# air_cylinder_control.net
KiCad netlist of a schematic drawn in Altium Designer
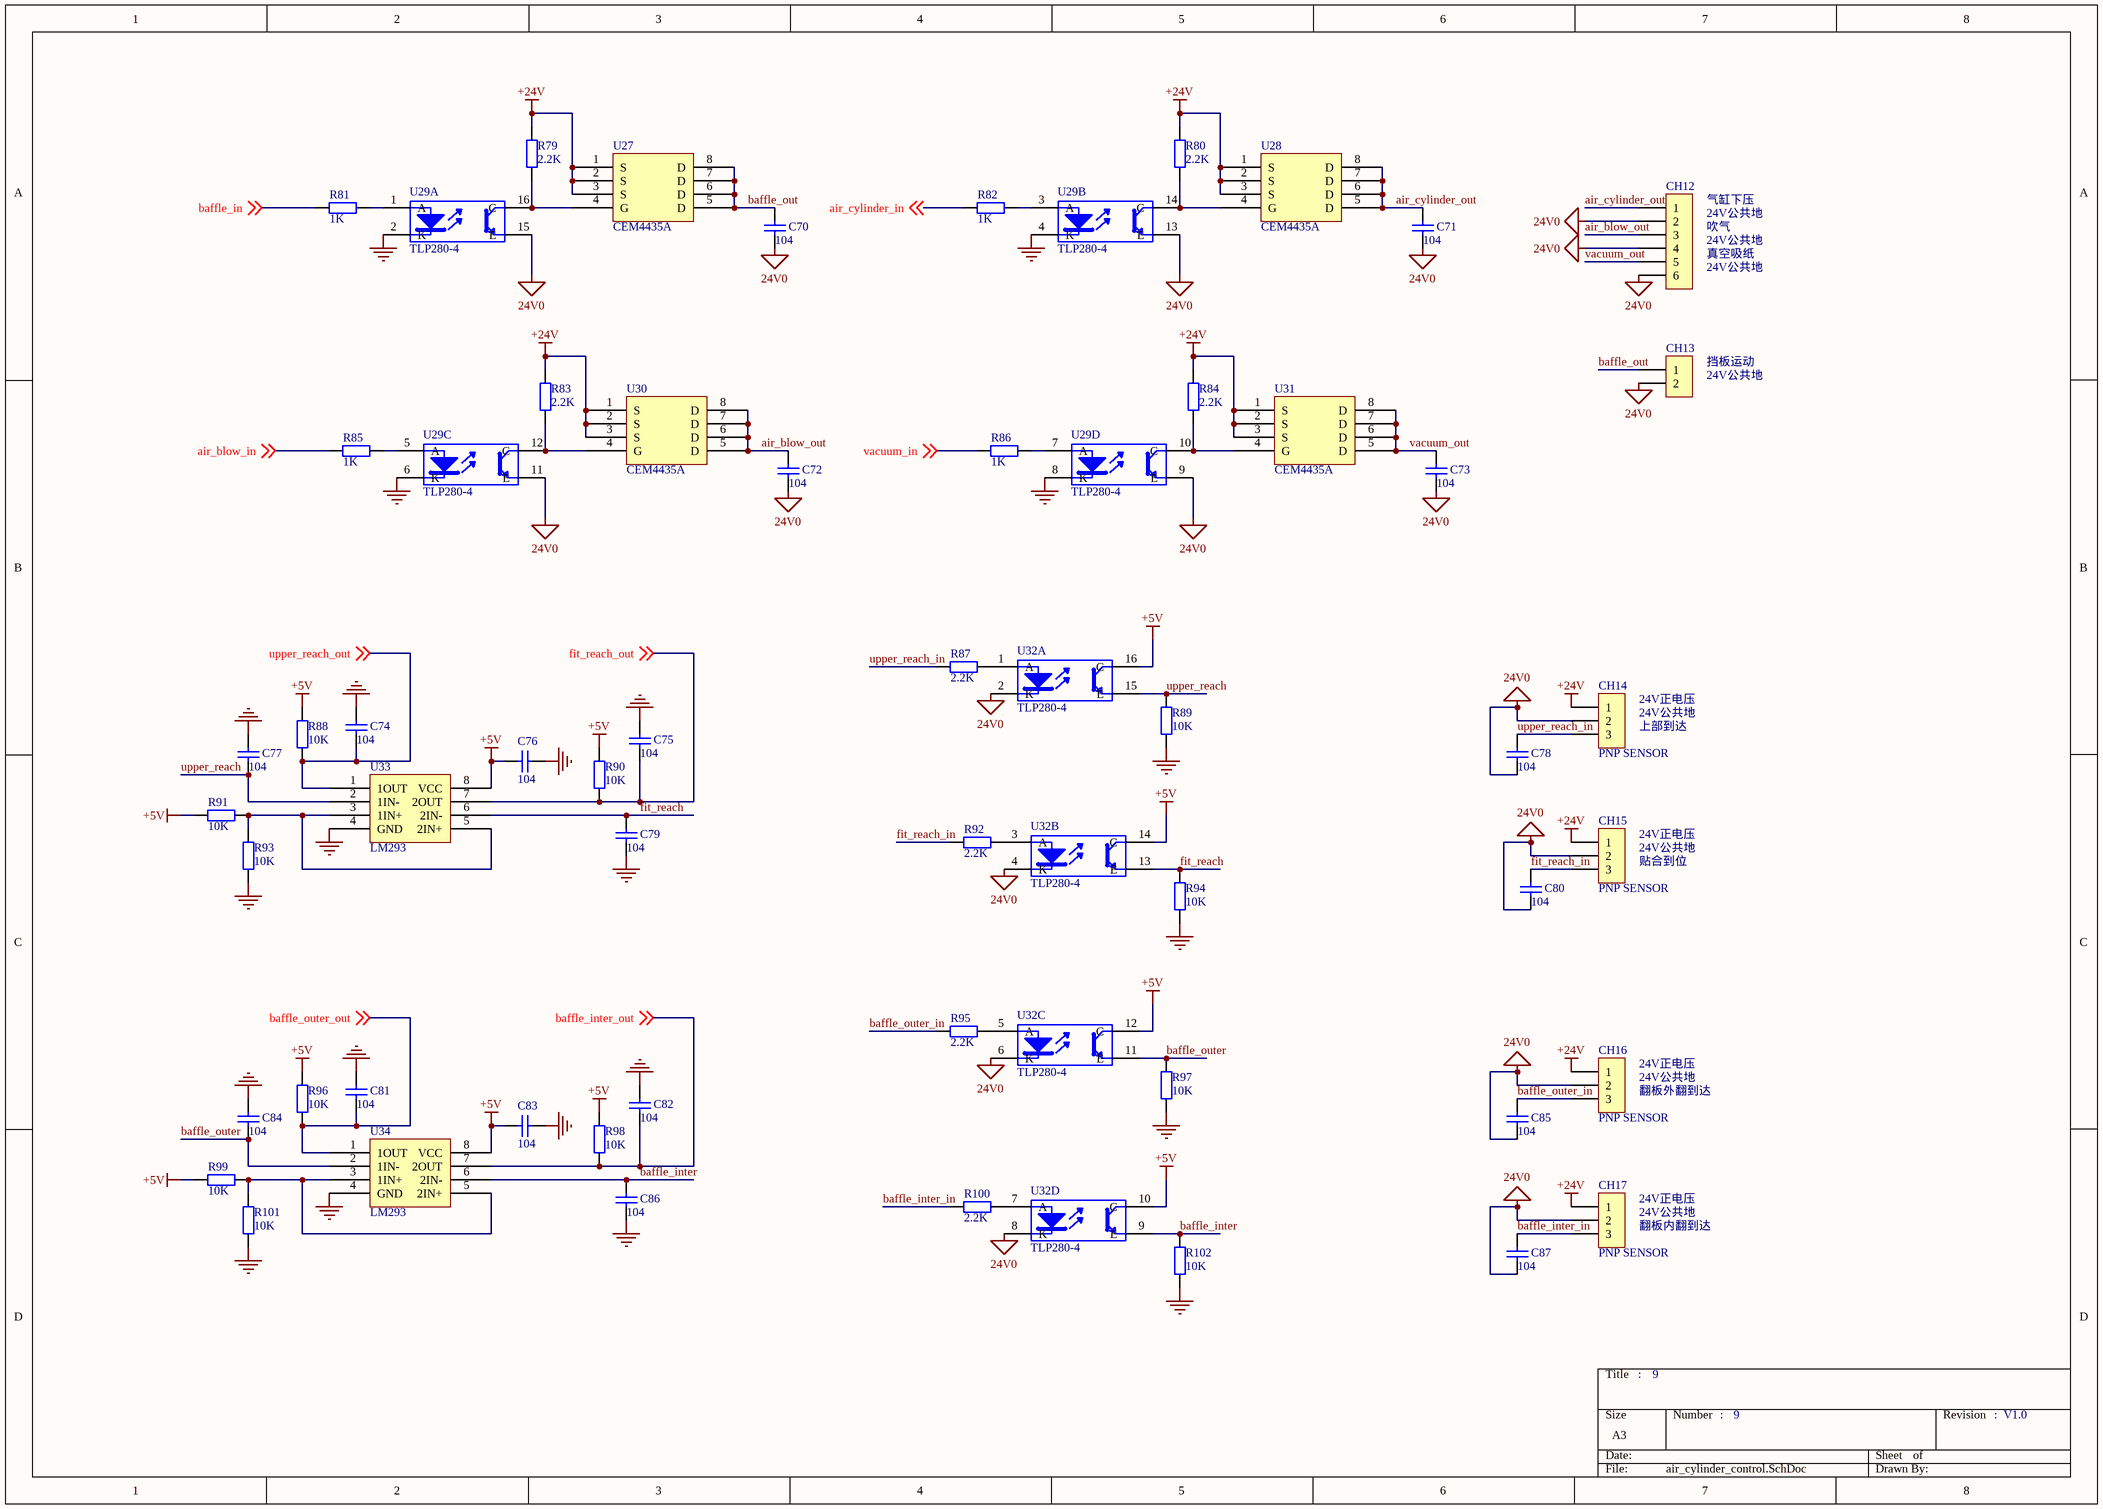
[diagram p0: air_cylinder_control.SchDoc]

(export (version "E")
  (design (tool "Eeschema 10.0.6"))
  (components
    (comp (ref "C70")
      (value "104")
      (footprint "0805")
      (description "Capacitor")
      (fields (field (name "Comment") "Cap") (field (name "PUBLISHER") "Altium Limited"))
      (libsource (lib "Miscellaneous Devices") (part "Cap"))
    )
    (comp (ref "C71")
      (value "104")
      (footprint "0805")
      (description "Capacitor")
      (fields (field (name "Comment") "Cap") (field (name "PUBLISHER") "Altium Limited"))
      (libsource (lib "Miscellaneous Devices") (part "Cap"))
    )
    (comp (ref "C72")
      (value "104")
      (footprint "0805")
      (description "Capacitor")
      (fields (field (name "Comment") "Cap") (field (name "PUBLISHER") "Altium Limited"))
      (libsource (lib "Miscellaneous Devices") (part "Cap"))
    )
    (comp (ref "C73")
      (value "104")
      (footprint "0805")
      (description "Capacitor")
      (fields (field (name "Comment") "Cap") (field (name "PUBLISHER") "Altium Limited"))
      (libsource (lib "Miscellaneous Devices") (part "Cap"))
    )
    (comp (ref "C74")
      (value "104")
      (footprint "0805")
      (description "Capacitor")
      (fields (field (name "Comment") "Cap") (field (name "PUBLISHER") "Altium Limited"))
      (libsource (lib "Miscellaneous Devices") (part "Cap"))
    )
    (comp (ref "C75")
      (value "104")
      (footprint "0805")
      (description "Capacitor")
      (fields (field (name "Comment") "Cap") (field (name "PUBLISHER") "Altium Limited"))
      (libsource (lib "Miscellaneous Devices") (part "Cap"))
    )
    (comp (ref "C76")
      (value "104")
      (footprint "0805")
      (description "Capacitor")
      (fields (field (name "Comment") "Cap") (field (name "PUBLISHER") "Altium Limited"))
      (libsource (lib "Miscellaneous Devices") (part "Cap"))
    )
    (comp (ref "C77")
      (value "104")
      (footprint "0805")
      (description "Capacitor")
      (fields (field (name "Comment") "Cap") (field (name "PUBLISHER") "Altium Limited"))
      (libsource (lib "Miscellaneous Devices") (part "Cap"))
    )
    (comp (ref "C78")
      (value "104")
      (footprint "0805")
      (description "Capacitor")
      (fields (field (name "Comment") "Cap") (field (name "PUBLISHER") "Altium Limited"))
      (libsource (lib "Miscellaneous Devices") (part "Cap"))
    )
    (comp (ref "C79")
      (value "104")
      (footprint "0805")
      (description "Capacitor")
      (fields (field (name "Comment") "Cap") (field (name "PUBLISHER") "Altium Limited"))
      (libsource (lib "Miscellaneous Devices") (part "Cap"))
    )
    (comp (ref "C80")
      (value "104")
      (footprint "0805")
      (description "Capacitor")
      (fields (field (name "Comment") "Cap") (field (name "PUBLISHER") "Altium Limited"))
      (libsource (lib "Miscellaneous Devices") (part "Cap"))
    )
    (comp (ref "C81")
      (value "104")
      (footprint "0805")
      (description "Capacitor")
      (fields (field (name "Comment") "Cap") (field (name "PUBLISHER") "Altium Limited"))
      (libsource (lib "Miscellaneous Devices") (part "Cap"))
    )
    (comp (ref "C82")
      (value "104")
      (footprint "0805")
      (description "Capacitor")
      (fields (field (name "Comment") "Cap") (field (name "PUBLISHER") "Altium Limited"))
      (libsource (lib "Miscellaneous Devices") (part "Cap"))
    )
    (comp (ref "C83")
      (value "104")
      (footprint "0805")
      (description "Capacitor")
      (fields (field (name "Comment") "Cap") (field (name "PUBLISHER") "Altium Limited"))
      (libsource (lib "Miscellaneous Devices") (part "Cap"))
    )
    (comp (ref "C84")
      (value "104")
      (footprint "0805")
      (description "Capacitor")
      (fields (field (name "Comment") "Cap") (field (name "PUBLISHER") "Altium Limited"))
      (libsource (lib "Miscellaneous Devices") (part "Cap"))
    )
    (comp (ref "C85")
      (value "104")
      (footprint "0805")
      (description "Capacitor")
      (fields (field (name "Comment") "Cap") (field (name "PUBLISHER") "Altium Limited"))
      (libsource (lib "Miscellaneous Devices") (part "Cap"))
    )
    (comp (ref "C86")
      (value "104")
      (footprint "0805")
      (description "Capacitor")
      (fields (field (name "Comment") "Cap") (field (name "PUBLISHER") "Altium Limited"))
      (libsource (lib "Miscellaneous Devices") (part "Cap"))
    )
    (comp (ref "C87")
      (value "104")
      (footprint "0805")
      (description "Capacitor")
      (fields (field (name "Comment") "Cap") (field (name "PUBLISHER") "Altium Limited"))
      (libsource (lib "Miscellaneous Devices") (part "Cap"))
    )
    (comp (ref "CH12")
      (value "HEADER1X6")
      (footprint "CH3.96-6PIN")
      (libsource (lib "myIntegrated_Library1") (part "HEADER1X6"))
    )
    (comp (ref "CH13")
      (value "HEADER1X2")
      (footprint "CH3.96-2PIN")
      (libsource (lib "myIntegrated_Library1") (part "HEADER1X2"))
    )
    (comp (ref "CH14")
      (value "HEADER1X3")
      (footprint "CH3.96-3PIN")
      (fields (field (name "ALTIUM_UNNAMED_1") "PNP SENSOR"))
      (libsource (lib "myIntegrated_Library1") (part "HEADER1X3"))
    )
    (comp (ref "CH15")
      (value "HEADER1X3")
      (footprint "CH3.96-3PIN")
      (fields (field (name "ALTIUM_UNNAMED_1") "PNP SENSOR"))
      (libsource (lib "myIntegrated_Library1") (part "HEADER1X3"))
    )
    (comp (ref "CH16")
      (value "HEADER1X3")
      (footprint "CH3.96-3PIN")
      (fields (field (name "ALTIUM_UNNAMED_1") "PNP SENSOR"))
      (libsource (lib "myIntegrated_Library1") (part "HEADER1X3"))
    )
    (comp (ref "CH17")
      (value "HEADER1X3")
      (footprint "CH3.96-3PIN")
      (fields (field (name "ALTIUM_UNNAMED_1") "PNP SENSOR"))
      (libsource (lib "myIntegrated_Library1") (part "HEADER1X3"))
    )
    (comp (ref "R79")
      (value "2.2K")
      (footprint "0805")
      (description "Resistor")
      (fields (field (name "Comment") "Res2") (field (name "PUBLISHER") "Altium Limited"))
      (libsource (lib "Miscellaneous Devices") (part "Res2"))
    )
    (comp (ref "R80")
      (value "2.2K")
      (footprint "0805")
      (description "Resistor")
      (fields (field (name "Comment") "Res2") (field (name "PUBLISHER") "Altium Limited"))
      (libsource (lib "Miscellaneous Devices") (part "Res2"))
    )
    (comp (ref "R81")
      (value "1K")
      (footprint "0805")
      (description "Resistor")
      (fields (field (name "Comment") "Res2") (field (name "PUBLISHER") "Altium Limited"))
      (libsource (lib "") (part "Res2_1"))
    )
    (comp (ref "R82")
      (value "1K")
      (footprint "0805")
      (description "Resistor")
      (fields (field (name "Comment") "Res2") (field (name "PUBLISHER") "Altium Limited"))
      (libsource (lib "") (part "Res2_1"))
    )
    (comp (ref "R83")
      (value "2.2K")
      (footprint "0805")
      (description "Resistor")
      (fields (field (name "Comment") "Res2") (field (name "PUBLISHER") "Altium Limited"))
      (libsource (lib "Miscellaneous Devices") (part "Res2"))
    )
    (comp (ref "R84")
      (value "2.2K")
      (footprint "0805")
      (description "Resistor")
      (fields (field (name "Comment") "Res2") (field (name "PUBLISHER") "Altium Limited"))
      (libsource (lib "Miscellaneous Devices") (part "Res2"))
    )
    (comp (ref "R85")
      (value "1K")
      (footprint "0805")
      (description "Resistor")
      (fields (field (name "Comment") "Res2") (field (name "PUBLISHER") "Altium Limited"))
      (libsource (lib "") (part "Res2_1"))
    )
    (comp (ref "R86")
      (value "1K")
      (footprint "0805")
      (description "Resistor")
      (fields (field (name "Comment") "Res2") (field (name "PUBLISHER") "Altium Limited"))
      (libsource (lib "") (part "Res2_1"))
    )
    (comp (ref "R87")
      (value "2.2K")
      (footprint "0805")
      (description "Resistor")
      (fields (field (name "Comment") "Res2") (field (name "PUBLISHER") "Altium Limited"))
      (libsource (lib "") (part "Res2_1"))
    )
    (comp (ref "R88")
      (value "10K")
      (footprint "0805")
      (description "Resistor")
      (fields (field (name "Comment") "Res2") (field (name "PUBLISHER") "Altium Limited"))
      (libsource (lib "") (part "Res2_3"))
    )
    (comp (ref "R89")
      (value "10K")
      (footprint "0805")
      (description "Resistor")
      (fields (field (name "Comment") "Res2") (field (name "PUBLISHER") "Altium Limited"))
      (libsource (lib "") (part "Res2_3"))
    )
    (comp (ref "R90")
      (value "10K")
      (footprint "0805")
      (description "Resistor")
      (fields (field (name "Comment") "Res2") (field (name "PUBLISHER") "Altium Limited"))
      (libsource (lib "") (part "Res2_3"))
    )
    (comp (ref "R91")
      (value "10K")
      (footprint "0805")
      (description "Resistor")
      (fields (field (name "Comment") "Res2") (field (name "PUBLISHER") "Altium Limited"))
      (libsource (lib "") (part "Res2_2"))
    )
    (comp (ref "R92")
      (value "2.2K")
      (footprint "0805")
      (description "Resistor")
      (fields (field (name "Comment") "Res2") (field (name "PUBLISHER") "Altium Limited"))
      (libsource (lib "") (part "Res2_1"))
    )
    (comp (ref "R93")
      (value "10K")
      (footprint "0805")
      (description "Resistor")
      (fields (field (name "Comment") "Res2") (field (name "PUBLISHER") "Altium Limited"))
      (libsource (lib "") (part "Res2_3"))
    )
    (comp (ref "R94")
      (value "10K")
      (footprint "0805")
      (description "Resistor")
      (fields (field (name "Comment") "Res2") (field (name "PUBLISHER") "Altium Limited"))
      (libsource (lib "") (part "Res2_3"))
    )
    (comp (ref "R95")
      (value "2.2K")
      (footprint "0805")
      (description "Resistor")
      (fields (field (name "Comment") "Res2") (field (name "PUBLISHER") "Altium Limited"))
      (libsource (lib "") (part "Res2_1"))
    )
    (comp (ref "R96")
      (value "10K")
      (footprint "0805")
      (description "Resistor")
      (fields (field (name "Comment") "Res2") (field (name "PUBLISHER") "Altium Limited"))
      (libsource (lib "") (part "Res2_3"))
    )
    (comp (ref "R97")
      (value "10K")
      (footprint "0805")
      (description "Resistor")
      (fields (field (name "Comment") "Res2") (field (name "PUBLISHER") "Altium Limited"))
      (libsource (lib "") (part "Res2_3"))
    )
    (comp (ref "R98")
      (value "10K")
      (footprint "0805")
      (description "Resistor")
      (fields (field (name "Comment") "Res2") (field (name "PUBLISHER") "Altium Limited"))
      (libsource (lib "") (part "Res2_3"))
    )
    (comp (ref "R99")
      (value "10K")
      (footprint "0805")
      (description "Resistor")
      (fields (field (name "Comment") "Res2") (field (name "PUBLISHER") "Altium Limited"))
      (libsource (lib "") (part "Res2_2"))
    )
    (comp (ref "R100")
      (value "2.2K")
      (footprint "0805")
      (description "Resistor")
      (fields (field (name "Comment") "Res2") (field (name "PUBLISHER") "Altium Limited"))
      (libsource (lib "") (part "Res2_1"))
    )
    (comp (ref "R101")
      (value "10K")
      (footprint "0805")
      (description "Resistor")
      (fields (field (name "Comment") "Res2") (field (name "PUBLISHER") "Altium Limited"))
      (libsource (lib "") (part "Res2_3"))
    )
    (comp (ref "R102")
      (value "10K")
      (footprint "0805")
      (description "Resistor")
      (fields (field (name "Comment") "Res2") (field (name "PUBLISHER") "Altium Limited"))
      (libsource (lib "") (part "Res2_3"))
    )
    (comp (ref "U27")
      (value "CEM4435A")
      (footprint "SOP8-OP27")
      (libsource (lib "myIntegrated_Library1") (part "CEM4435A"))
    )
    (comp (ref "U28")
      (value "CEM4435A")
      (footprint "SOP8-OP27")
      (libsource (lib "myIntegrated_Library1") (part "CEM4435A"))
    )
    (comp (ref "U29") (value "TLP280-4") (footprint "SO16") (libsource (lib "WH V20") (part "TLP521-4")))
    (comp (ref "U30")
      (value "CEM4435A")
      (footprint "SOP8-OP27")
      (libsource (lib "myIntegrated_Library1") (part "CEM4435A"))
    )
    (comp (ref "U31")
      (value "CEM4435A")
      (footprint "SOP8-OP27")
      (libsource (lib "myIntegrated_Library1") (part "CEM4435A"))
    )
    (comp (ref "U32") (value "TLP280-4") (footprint "SO16") (libsource (lib "WH V20") (part "TLP521-4")))
    (comp (ref "U33")
      (value "LM293")
      (footprint "SOP8-OP27")
      (libsource (lib "myIntegrated_Library1") (part "LM293"))
    )
    (comp (ref "U34")
      (value "LM293")
      (footprint "SOP8-OP27")
      (libsource (lib "myIntegrated_Library1") (part "LM293"))
    )
  )
  (nets
    (net (code "1") (name "+5V") (class "Default")
      (node (ref "C76") (pin "2") (pinfunction "2_2") (pintype "passive"))
      (node (ref "C83") (pin "2") (pinfunction "2_2") (pintype "passive"))
      (node (ref "R88") (pin "2") (pinfunction "2_2") (pintype "passive"))
      (node (ref "R90") (pin "2") (pinfunction "2_2") (pintype "passive"))
      (node (ref "R91") (pin "2") (pinfunction "2_2") (pintype "passive"))
      (node (ref "R96") (pin "2") (pinfunction "2_2") (pintype "passive"))
      (node (ref "R98") (pin "2") (pinfunction "2_2") (pintype "passive"))
      (node (ref "R99") (pin "2") (pinfunction "2_2") (pintype "passive"))
      (node (ref "U32") (pin "10") (pinfunction "C_10") (pintype "passive"))
      (node (ref "U32") (pin "12") (pinfunction "C_12") (pintype "passive"))
      (node (ref "U32") (pin "14") (pinfunction "C_14") (pintype "passive"))
      (node (ref "U32") (pin "16") (pinfunction "C_16") (pintype "passive"))
      (node (ref "U33") (pin "8") (pinfunction "VCC_8") (pintype "passive"))
      (node (ref "U34") (pin "8") (pinfunction "VCC_8") (pintype "passive"))
    )
    (net (code "2") (name "+24V") (class "Default")
      (node (ref "CH14") (pin "1") (pinfunction "1_1") (pintype "passive"))
      (node (ref "CH15") (pin "1") (pinfunction "1_1") (pintype "passive"))
      (node (ref "CH16") (pin "1") (pinfunction "1_1") (pintype "passive"))
      (node (ref "CH17") (pin "1") (pinfunction "1_1") (pintype "passive"))
      (node (ref "R79") (pin "1") (pinfunction "1_1") (pintype "passive"))
      (node (ref "R80") (pin "1") (pinfunction "1_1") (pintype "passive"))
      (node (ref "R83") (pin "1") (pinfunction "1_1") (pintype "passive"))
      (node (ref "R84") (pin "1") (pinfunction "1_1") (pintype "passive"))
      (node (ref "U27") (pin "1") (pinfunction "S_1") (pintype "passive"))
      (node (ref "U27") (pin "2") (pinfunction "S_2") (pintype "passive"))
      (node (ref "U27") (pin "3") (pinfunction "S_3") (pintype "passive"))
      (node (ref "U28") (pin "1") (pinfunction "S_1") (pintype "passive"))
      (node (ref "U28") (pin "2") (pinfunction "S_2") (pintype "passive"))
      (node (ref "U28") (pin "3") (pinfunction "S_3") (pintype "passive"))
      (node (ref "U30") (pin "1") (pinfunction "S_1") (pintype "passive"))
      (node (ref "U30") (pin "2") (pinfunction "S_2") (pintype "passive"))
      (node (ref "U30") (pin "3") (pinfunction "S_3") (pintype "passive"))
      (node (ref "U31") (pin "1") (pinfunction "S_1") (pintype "passive"))
      (node (ref "U31") (pin "2") (pinfunction "S_2") (pintype "passive"))
      (node (ref "U31") (pin "3") (pinfunction "S_3") (pintype "passive"))
    )
    (net (code "3") (name "/air_blow_out") (class "Default")
      (node (ref "C72") (pin "2") (pinfunction "2_2") (pintype "passive"))
      (node (ref "CH12") (pin "3") (pinfunction "3_3") (pintype "passive"))
      (node (ref "U30") (pin "5") (pinfunction "D_5") (pintype "passive"))
      (node (ref "U30") (pin "6") (pinfunction "D_6") (pintype "passive"))
      (node (ref "U30") (pin "7") (pinfunction "D_7") (pintype "passive"))
      (node (ref "U30") (pin "8") (pinfunction "D_8") (pintype "passive"))
    )
    (net (code "4") (name "/air_cylinder_out") (class "Default")
      (node (ref "C71") (pin "2") (pinfunction "2_2") (pintype "passive"))
      (node (ref "CH12") (pin "1") (pinfunction "1_1") (pintype "passive"))
      (node (ref "U28") (pin "5") (pinfunction "D_5") (pintype "passive"))
      (node (ref "U28") (pin "6") (pinfunction "D_6") (pintype "passive"))
      (node (ref "U28") (pin "7") (pinfunction "D_7") (pintype "passive"))
      (node (ref "U28") (pin "8") (pinfunction "D_8") (pintype "passive"))
    )
    (net (code "5") (name "/baffle_inter") (class "Default")
      (node (ref "C86") (pin "2") (pinfunction "2_2") (pintype "passive"))
      (node (ref "R102") (pin "2") (pinfunction "2_2") (pintype "passive"))
      (node (ref "U32") (pin "9") (pinfunction "E_9") (pintype "passive"))
      (node (ref "U34") (pin "6") (pinfunction "2IN-_6") (pintype "passive"))
    )
    (net (code "6") (name "/baffle_inter_in") (class "Default")
      (node (ref "C87") (pin "2") (pinfunction "2_2") (pintype "passive"))
      (node (ref "CH17") (pin "3") (pinfunction "3_3") (pintype "passive"))
      (node (ref "R100") (pin "1") (pinfunction "1_1") (pintype "passive"))
    )
    (net (code "7") (name "/baffle_out") (class "Default")
      (node (ref "C70") (pin "2") (pinfunction "2_2") (pintype "passive"))
      (node (ref "CH13") (pin "1") (pinfunction "1_1") (pintype "passive"))
      (node (ref "U27") (pin "5") (pinfunction "D_5") (pintype "passive"))
      (node (ref "U27") (pin "6") (pinfunction "D_6") (pintype "passive"))
      (node (ref "U27") (pin "7") (pinfunction "D_7") (pintype "passive"))
      (node (ref "U27") (pin "8") (pinfunction "D_8") (pintype "passive"))
    )
    (net (code "8") (name "/baffle_outer") (class "Default")
      (node (ref "C84") (pin "1") (pinfunction "1_1") (pintype "passive"))
      (node (ref "R97") (pin "2") (pinfunction "2_2") (pintype "passive"))
      (node (ref "U32") (pin "11") (pinfunction "E_11") (pintype "passive"))
      (node (ref "U34") (pin "2") (pinfunction "1IN-_2") (pintype "passive"))
    )
    (net (code "9") (name "/baffle_outer_in") (class "Default")
      (node (ref "C85") (pin "2") (pinfunction "2_2") (pintype "passive"))
      (node (ref "CH16") (pin "3") (pinfunction "3_3") (pintype "passive"))
      (node (ref "R95") (pin "1") (pinfunction "1_1") (pintype "passive"))
    )
    (net (code "10") (name "/fit_reach") (class "Default")
      (node (ref "C79") (pin "2") (pinfunction "2_2") (pintype "passive"))
      (node (ref "R94") (pin "2") (pinfunction "2_2") (pintype "passive"))
      (node (ref "U32") (pin "13") (pinfunction "E_13") (pintype "passive"))
      (node (ref "U33") (pin "6") (pinfunction "2IN-_6") (pintype "passive"))
    )
    (net (code "11") (name "/fit_reach_in") (class "Default")
      (node (ref "C80") (pin "2") (pinfunction "2_2") (pintype "passive"))
      (node (ref "CH15") (pin "3") (pinfunction "3_3") (pintype "passive"))
      (node (ref "R92") (pin "1") (pinfunction "1_1") (pintype "passive"))
    )
    (net (code "12") (name "/upper_reach") (class "Default")
      (node (ref "C77") (pin "1") (pinfunction "1_1") (pintype "passive"))
      (node (ref "R89") (pin "2") (pinfunction "2_2") (pintype "passive"))
      (node (ref "U32") (pin "15") (pinfunction "E_15") (pintype "passive"))
      (node (ref "U33") (pin "2") (pinfunction "1IN-_2") (pintype "passive"))
    )
    (net (code "13") (name "/upper_reach_in") (class "Default")
      (node (ref "C78") (pin "2") (pinfunction "2_2") (pintype "passive"))
      (node (ref "CH14") (pin "3") (pinfunction "3_3") (pintype "passive"))
      (node (ref "R87") (pin "1") (pinfunction "1_1") (pintype "passive"))
    )
    (net (code "14") (name "/vacuum_out") (class "Default")
      (node (ref "C73") (pin "2") (pinfunction "2_2") (pintype "passive"))
      (node (ref "CH12") (pin "5") (pinfunction "5_5") (pintype "passive"))
      (node (ref "U31") (pin "5") (pinfunction "D_5") (pintype "passive"))
      (node (ref "U31") (pin "6") (pinfunction "D_6") (pintype "passive"))
      (node (ref "U31") (pin "7") (pinfunction "D_7") (pintype "passive"))
      (node (ref "U31") (pin "8") (pinfunction "D_8") (pintype "passive"))
    )
    (net (code "15") (name "24V0") (class "Default")
      (node (ref "C70") (pin "1") (pinfunction "1_1") (pintype "passive"))
      (node (ref "C71") (pin "1") (pinfunction "1_1") (pintype "passive"))
      (node (ref "C72") (pin "1") (pinfunction "1_1") (pintype "passive"))
      (node (ref "C73") (pin "1") (pinfunction "1_1") (pintype "passive"))
      (node (ref "C78") (pin "1") (pinfunction "1_1") (pintype "passive"))
      (node (ref "C80") (pin "1") (pinfunction "1_1") (pintype "passive"))
      (node (ref "C85") (pin "1") (pinfunction "1_1") (pintype "passive"))
      (node (ref "C87") (pin "1") (pinfunction "1_1") (pintype "passive"))
      (node (ref "CH12") (pin "2") (pinfunction "2_2") (pintype "passive"))
      (node (ref "CH12") (pin "4") (pinfunction "4_4") (pintype "passive"))
      (node (ref "CH12") (pin "6") (pinfunction "6_6") (pintype "passive"))
      (node (ref "CH13") (pin "2") (pinfunction "2_2") (pintype "passive"))
      (node (ref "CH14") (pin "2") (pinfunction "2_2") (pintype "passive"))
      (node (ref "CH15") (pin "2") (pinfunction "2_2") (pintype "passive"))
      (node (ref "CH16") (pin "2") (pinfunction "2_2") (pintype "passive"))
      (node (ref "CH17") (pin "2") (pinfunction "2_2") (pintype "passive"))
      (node (ref "U29") (pin "11") (pinfunction "E_11") (pintype "passive"))
      (node (ref "U29") (pin "13") (pinfunction "E_13") (pintype "passive"))
      (node (ref "U29") (pin "15") (pinfunction "E_15") (pintype "passive"))
      (node (ref "U29") (pin "9") (pinfunction "E_9") (pintype "passive"))
      (node (ref "U32") (pin "2") (pinfunction "K_2") (pintype "passive"))
      (node (ref "U32") (pin "4") (pinfunction "K_4") (pintype "passive"))
      (node (ref "U32") (pin "6") (pinfunction "K_6") (pintype "passive"))
      (node (ref "U32") (pin "8") (pinfunction "K_8") (pintype "passive"))
    )
    (net (code "16") (name "GND") (class "Default")
      (node (ref "C74") (pin "2") (pinfunction "2_2") (pintype "passive"))
      (node (ref "C75") (pin "2") (pinfunction "2_2") (pintype "passive"))
      (node (ref "C76") (pin "1") (pinfunction "1_1") (pintype "passive"))
      (node (ref "C77") (pin "2") (pinfunction "2_2") (pintype "passive"))
      (node (ref "C79") (pin "1") (pinfunction "1_1") (pintype "passive"))
      (node (ref "C81") (pin "2") (pinfunction "2_2") (pintype "passive"))
      (node (ref "C82") (pin "2") (pinfunction "2_2") (pintype "passive"))
      (node (ref "C83") (pin "1") (pinfunction "1_1") (pintype "passive"))
      (node (ref "C84") (pin "2") (pinfunction "2_2") (pintype "passive"))
      (node (ref "C86") (pin "1") (pinfunction "1_1") (pintype "passive"))
      (node (ref "R101") (pin "1") (pinfunction "1_1") (pintype "passive"))
      (node (ref "R102") (pin "1") (pinfunction "1_1") (pintype "passive"))
      (node (ref "R89") (pin "1") (pinfunction "1_1") (pintype "passive"))
      (node (ref "R93") (pin "1") (pinfunction "1_1") (pintype "passive"))
      (node (ref "R94") (pin "1") (pinfunction "1_1") (pintype "passive"))
      (node (ref "R97") (pin "1") (pinfunction "1_1") (pintype "passive"))
      (node (ref "U29") (pin "2") (pinfunction "K_2") (pintype "passive"))
      (node (ref "U29") (pin "4") (pinfunction "K_4") (pintype "passive"))
      (node (ref "U29") (pin "6") (pinfunction "K_6") (pintype "passive"))
      (node (ref "U29") (pin "8") (pinfunction "K_8") (pintype "passive"))
      (node (ref "U33") (pin "4") (pinfunction "GND_4") (pintype "passive"))
      (node (ref "U34") (pin "4") (pinfunction "GND_4") (pintype "passive"))
    )
    (net (code "17") (name "Net-(U27-G)") (class "Default")
      (node (ref "R79") (pin "2") (pinfunction "2_2") (pintype "passive"))
      (node (ref "U27") (pin "4") (pinfunction "G_4") (pintype "passive"))
      (node (ref "U29") (pin "16") (pinfunction "C_16") (pintype "passive"))
    )
    (net (code "18") (name "Net-(U28-G)") (class "Default")
      (node (ref "R80") (pin "2") (pinfunction "2_2") (pintype "passive"))
      (node (ref "U28") (pin "4") (pinfunction "G_4") (pintype "passive"))
      (node (ref "U29") (pin "14") (pinfunction "C_14") (pintype "passive"))
    )
    (net (code "19") (name "Net-(U29A-A)") (class "Default")
      (node (ref "R81") (pin "2") (pinfunction "2_2") (pintype "passive"))
      (node (ref "U29") (pin "1") (pinfunction "A_1") (pintype "passive"))
    )
    (net (code "20") (name "Net-(U29B-A)") (class "Default")
      (node (ref "R82") (pin "2") (pinfunction "2_2") (pintype "passive"))
      (node (ref "U29") (pin "3") (pinfunction "A_3") (pintype "passive"))
    )
    (net (code "21") (name "Net-(U29C-A)") (class "Default")
      (node (ref "R85") (pin "2") (pinfunction "2_2") (pintype "passive"))
      (node (ref "U29") (pin "5") (pinfunction "A_5") (pintype "passive"))
    )
    (net (code "22") (name "Net-(U29C-C)") (class "Default")
      (node (ref "R83") (pin "2") (pinfunction "2_2") (pintype "passive"))
      (node (ref "U29") (pin "12") (pinfunction "C_12") (pintype "passive"))
      (node (ref "U30") (pin "4") (pinfunction "G_4") (pintype "passive"))
    )
    (net (code "23") (name "Net-(U29D-A)") (class "Default")
      (node (ref "R86") (pin "2") (pinfunction "2_2") (pintype "passive"))
      (node (ref "U29") (pin "7") (pinfunction "A_7") (pintype "passive"))
    )
    (net (code "24") (name "Net-(U29D-C)") (class "Default")
      (node (ref "R84") (pin "2") (pinfunction "2_2") (pintype "passive"))
      (node (ref "U29") (pin "10") (pinfunction "C_10") (pintype "passive"))
      (node (ref "U31") (pin "4") (pinfunction "G_4") (pintype "passive"))
    )
    (net (code "25") (name "Net-(U32A-A)") (class "Default")
      (node (ref "R87") (pin "2") (pinfunction "2_2") (pintype "passive"))
      (node (ref "U32") (pin "1") (pinfunction "A_1") (pintype "passive"))
    )
    (net (code "26") (name "Net-(U32B-A)") (class "Default")
      (node (ref "R92") (pin "2") (pinfunction "2_2") (pintype "passive"))
      (node (ref "U32") (pin "3") (pinfunction "A_3") (pintype "passive"))
    )
    (net (code "27") (name "Net-(U32C-A)") (class "Default")
      (node (ref "R95") (pin "2") (pinfunction "2_2") (pintype "passive"))
      (node (ref "U32") (pin "5") (pinfunction "A_5") (pintype "passive"))
    )
    (net (code "28") (name "Net-(U32D-A)") (class "Default")
      (node (ref "R100") (pin "2") (pinfunction "2_2") (pintype "passive"))
      (node (ref "U32") (pin "7") (pinfunction "A_7") (pintype "passive"))
    )
    (net (code "29") (name "Net-(U33-1IN+)") (class "Default")
      (node (ref "R91") (pin "1") (pinfunction "1_1") (pintype "passive"))
      (node (ref "R93") (pin "2") (pinfunction "2_2") (pintype "passive"))
      (node (ref "U33") (pin "3") (pinfunction "1IN+_3") (pintype "passive"))
      (node (ref "U33") (pin "5") (pinfunction "2IN+_5") (pintype "passive"))
    )
    (net (code "30") (name "Net-(U34-1IN+)") (class "Default")
      (node (ref "R101") (pin "2") (pinfunction "2_2") (pintype "passive"))
      (node (ref "R99") (pin "1") (pinfunction "1_1") (pintype "passive"))
      (node (ref "U34") (pin "3") (pinfunction "1IN+_3") (pintype "passive"))
      (node (ref "U34") (pin "5") (pinfunction "2IN+_5") (pintype "passive"))
    )
    (net (code "31") (name "air_blow_in") (class "Default")
      (node (ref "R85") (pin "1") (pinfunction "1_1") (pintype "passive"))
    )
    (net (code "32") (name "air_cylinder_in") (class "Default")
      (node (ref "R82") (pin "1") (pinfunction "1_1") (pintype "passive"))
    )
    (net (code "33") (name "baffle_in") (class "Default")
      (node (ref "R81") (pin "1") (pinfunction "1_1") (pintype "passive"))
    )
    (net (code "34") (name "baffle_inter_out") (class "Default")
      (node (ref "C82") (pin "1") (pinfunction "1_1") (pintype "passive"))
      (node (ref "R98") (pin "1") (pinfunction "1_1") (pintype "passive"))
      (node (ref "U34") (pin "7") (pinfunction "2OUT_7") (pintype "passive"))
    )
    (net (code "35") (name "baffle_outer_out") (class "Default")
      (node (ref "C81") (pin "1") (pinfunction "1_1") (pintype "passive"))
      (node (ref "R96") (pin "1") (pinfunction "1_1") (pintype "passive"))
      (node (ref "U34") (pin "1") (pinfunction "1OUT_1") (pintype "passive"))
    )
    (net (code "36") (name "fit_reach_out") (class "Default")
      (node (ref "C75") (pin "1") (pinfunction "1_1") (pintype "passive"))
      (node (ref "R90") (pin "1") (pinfunction "1_1") (pintype "passive"))
      (node (ref "U33") (pin "7") (pinfunction "2OUT_7") (pintype "passive"))
    )
    (net (code "37") (name "upper_reach_out") (class "Default")
      (node (ref "C74") (pin "1") (pinfunction "1_1") (pintype "passive"))
      (node (ref "R88") (pin "1") (pinfunction "1_1") (pintype "passive"))
      (node (ref "U33") (pin "1") (pinfunction "1OUT_1") (pintype "passive"))
    )
    (net (code "38") (name "vacuum_in") (class "Default")
      (node (ref "R86") (pin "1") (pinfunction "1_1") (pintype "passive"))
    )
  )
)
